# Zypher_PCB.net
KiCad netlist of a schematic drawn in EAGLE
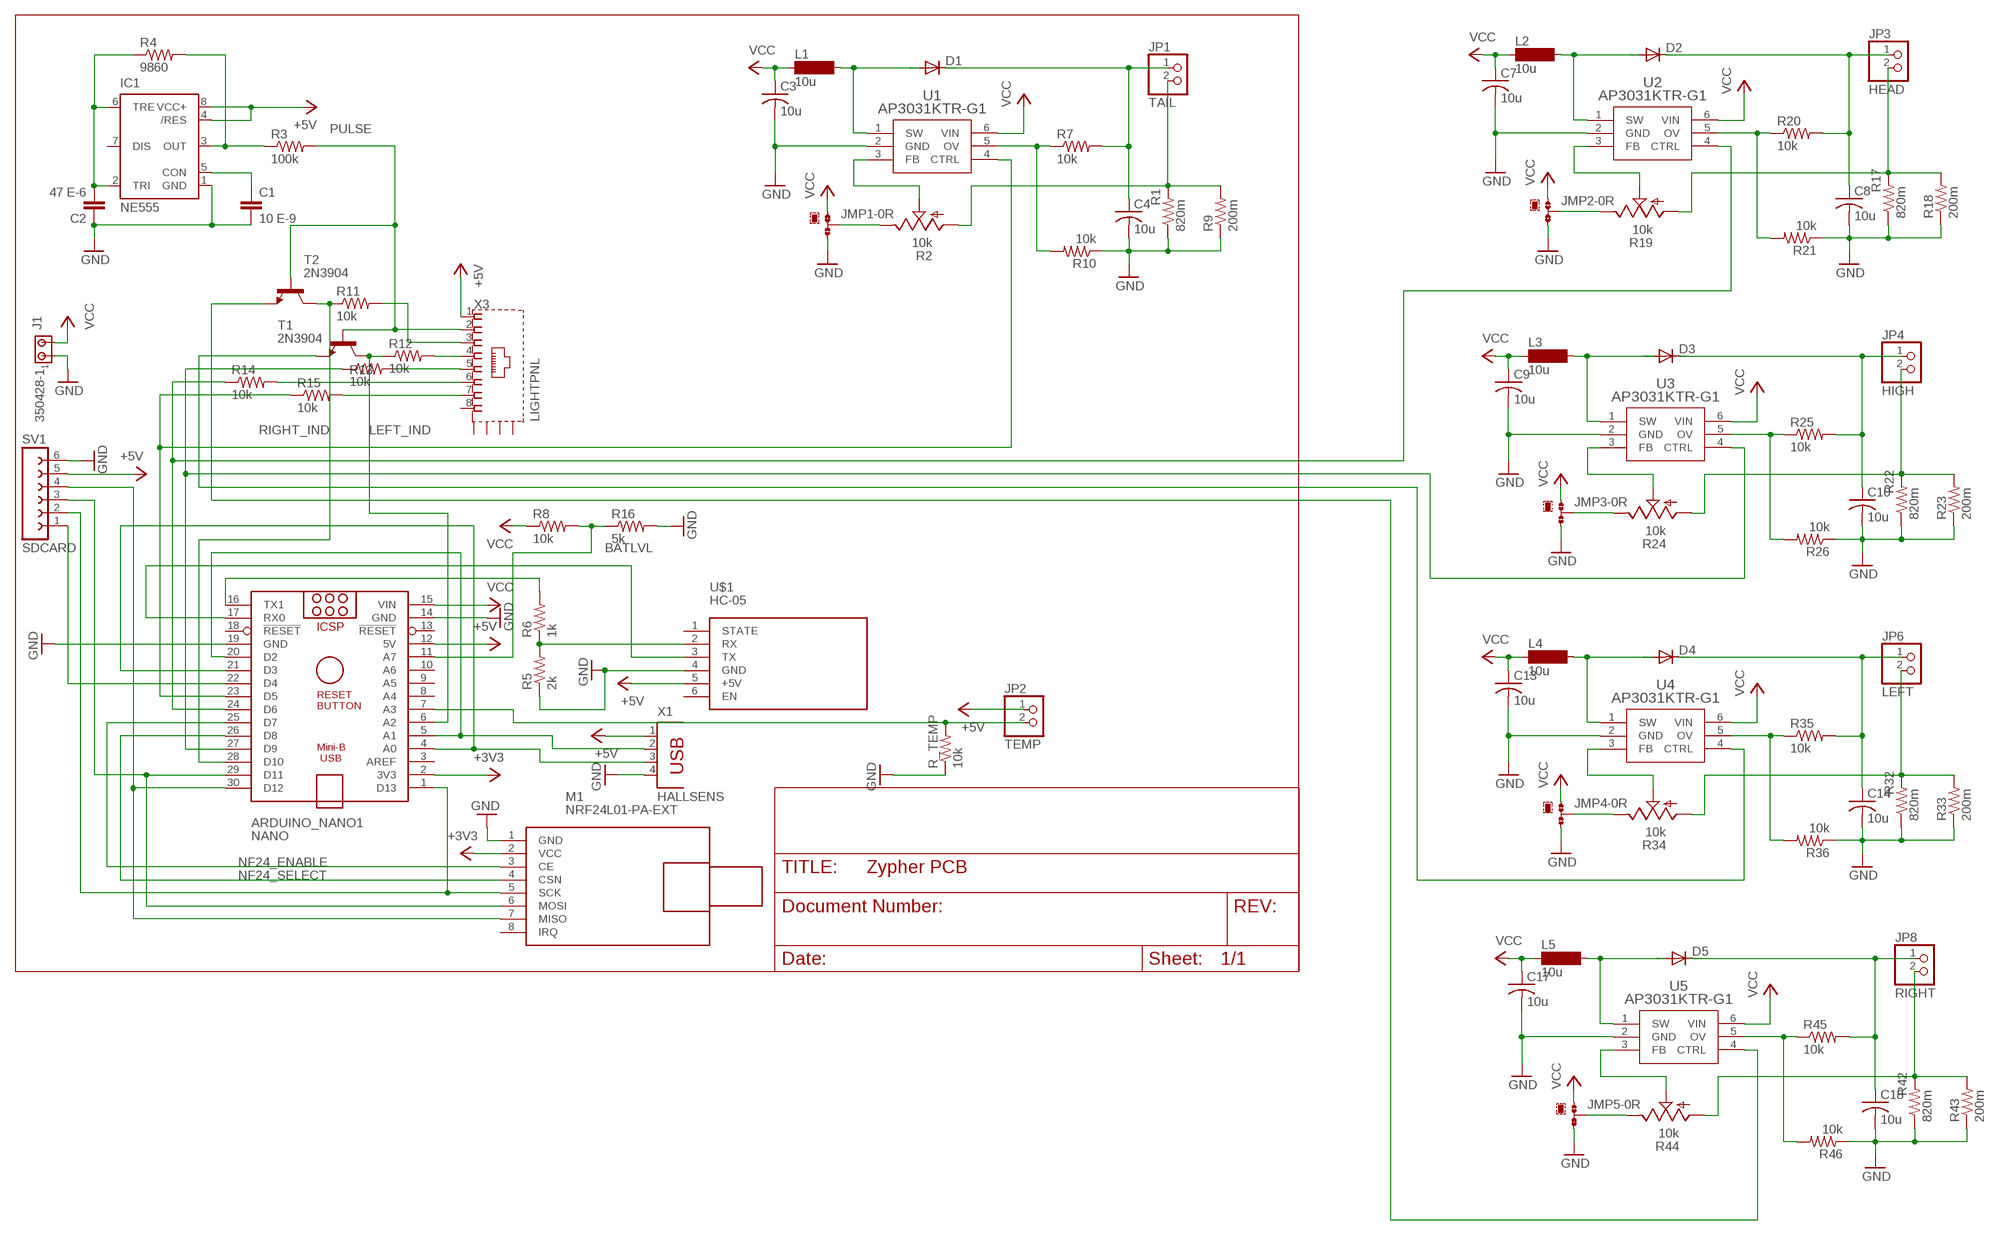
[diagram p0: schematic, sheet 1]

(export (version "E")
  (design (tool "Eeschema 10.0.6"))
  (components
    (comp (ref "ARDUINO_NANO1")
      (value "NANO")
      (footprint "eagle-import:ARDUINO_NANO")
      (libsource (lib "eagle-import") (part "ARDUINO_NANO"))
    )
    (comp (ref "C1")
      (value "10 E-9")
      (footprint "eagle-import:C2.5-5")
      (libsource (lib "eagle-import") (part "C2.5/5"))
    )
    (comp (ref "C2")
      (value "47 E-6")
      (footprint "eagle-import:C2.5-5")
      (libsource (lib "eagle-import") (part "C2.5/5"))
    )
    (comp (ref "C3")
      (value "10u")
      (footprint "eagle-import:C1206K")
      (libsource (lib "eagle-import") (part "C-USC1206K"))
    )
    (comp (ref "C4")
      (value "10u")
      (footprint "eagle-import:C1206K")
      (libsource (lib "eagle-import") (part "C-USC1206K"))
    )
    (comp (ref "C7")
      (value "10u")
      (footprint "eagle-import:C1206K")
      (libsource (lib "eagle-import") (part "C-USC1206K"))
    )
    (comp (ref "C8")
      (value "10u")
      (footprint "eagle-import:C1206K")
      (libsource (lib "eagle-import") (part "C-USC1206K"))
    )
    (comp (ref "C9")
      (value "10u")
      (footprint "eagle-import:C1206K")
      (libsource (lib "eagle-import") (part "C-USC1206K"))
    )
    (comp (ref "C10")
      (value "10u")
      (footprint "eagle-import:C1206K")
      (libsource (lib "eagle-import") (part "C-USC1206K"))
    )
    (comp (ref "C13")
      (value "10u")
      (footprint "eagle-import:C1206K")
      (libsource (lib "eagle-import") (part "C-USC1206K"))
    )
    (comp (ref "C14")
      (value "10u")
      (footprint "eagle-import:C1206K")
      (libsource (lib "eagle-import") (part "C-USC1206K"))
    )
    (comp (ref "C17")
      (value "10u")
      (footprint "eagle-import:C1206K")
      (libsource (lib "eagle-import") (part "C-USC1206K"))
    )
    (comp (ref "C18")
      (value "10u")
      (footprint "eagle-import:C1206K")
      (libsource (lib "eagle-import") (part "C-USC1206K"))
    )
    (comp (ref "D1")
      (value "DIODE-DO-214AC")
      (footprint "eagle-import:DO-214AC")
      (libsource (lib "eagle-import") (part "DIODE-DO-214AC"))
    )
    (comp (ref "D2")
      (value "DIODE-DO-214AC")
      (footprint "eagle-import:DO-214AC")
      (libsource (lib "eagle-import") (part "DIODE-DO-214AC"))
    )
    (comp (ref "D3")
      (value "DIODE-DO-214AC")
      (footprint "eagle-import:DO-214AC")
      (libsource (lib "eagle-import") (part "DIODE-DO-214AC"))
    )
    (comp (ref "D4")
      (value "DIODE-DO-214AC")
      (footprint "eagle-import:DO-214AC")
      (libsource (lib "eagle-import") (part "DIODE-DO-214AC"))
    )
    (comp (ref "D5")
      (value "DIODE-DO-214AC")
      (footprint "eagle-import:DO-214AC")
      (libsource (lib "eagle-import") (part "DIODE-DO-214AC"))
    )
    (comp (ref "IC1")
      (value "NE555")
      (footprint "eagle-import:DIL-08")
      (fields (field (name "MF") "Arrow Electronics") (field (name "MPN") "NE555N"))
      (libsource (lib "eagle-import") (part "NE555"))
    )
    (comp (ref "J1")
      (value "350428-1")
      (footprint "eagle-import:350428-1")
      (libsource (lib "eagle-import") (part "350428-1"))
    )
    (comp (ref "JMP1")
      (value "0R-JUMPA")
      (footprint "eagle-import:A0R-JMP")
      (libsource (lib "eagle-import") (part "0R-JUMPA"))
    )
    (comp (ref "JMP2")
      (value "0R-JUMPA")
      (footprint "eagle-import:A0R-JMP")
      (libsource (lib "eagle-import") (part "0R-JUMPA"))
    )
    (comp (ref "JMP3")
      (value "0R-JUMPA")
      (footprint "eagle-import:A0R-JMP")
      (libsource (lib "eagle-import") (part "0R-JUMPA"))
    )
    (comp (ref "JMP4")
      (value "0R-JUMPA")
      (footprint "eagle-import:A0R-JMP")
      (libsource (lib "eagle-import") (part "0R-JUMPA"))
    )
    (comp (ref "JMP5")
      (value "0R-JUMPA")
      (footprint "eagle-import:A0R-JMP")
      (libsource (lib "eagle-import") (part "0R-JUMPA"))
    )
    (comp (ref "JP1")
      (value "TAIL")
      (footprint "eagle-import:1X02")
      (libsource (lib "eagle-import") (part "PINHD-1X2"))
    )
    (comp (ref "JP2")
      (value "TEMP")
      (footprint "eagle-import:1X02")
      (libsource (lib "eagle-import") (part "PINHD-1X2"))
    )
    (comp (ref "JP3")
      (value "HEAD")
      (footprint "eagle-import:1X02")
      (libsource (lib "eagle-import") (part "PINHD-1X2"))
    )
    (comp (ref "JP4")
      (value "HIGH")
      (footprint "eagle-import:1X02")
      (libsource (lib "eagle-import") (part "PINHD-1X2"))
    )
    (comp (ref "JP6")
      (value "LEFT")
      (footprint "eagle-import:1X02")
      (libsource (lib "eagle-import") (part "PINHD-1X2"))
    )
    (comp (ref "JP8")
      (value "RIGHT")
      (footprint "eagle-import:1X02")
      (libsource (lib "eagle-import") (part "PINHD-1X2"))
    )
    (comp (ref "L1")
      (value "10u")
      (footprint "eagle-import:SD12K100")
      (libsource (lib "eagle-import") (part "SD12K100"))
    )
    (comp (ref "L2")
      (value "10u")
      (footprint "eagle-import:SD12K100")
      (libsource (lib "eagle-import") (part "SD12K100"))
    )
    (comp (ref "L3")
      (value "10u")
      (footprint "eagle-import:SD12K100")
      (libsource (lib "eagle-import") (part "SD12K100"))
    )
    (comp (ref "L4")
      (value "10u")
      (footprint "eagle-import:SD12K100")
      (libsource (lib "eagle-import") (part "SD12K100"))
    )
    (comp (ref "L5")
      (value "10u")
      (footprint "eagle-import:SD12K100")
      (libsource (lib "eagle-import") (part "SD12K100"))
    )
    (comp (ref "M1")
      (value "NRF24L01-PA-EXT")
      (footprint "eagle-import:WIRELESS-NRF24L01-PA-EXT")
      (libsource (lib "eagle-import") (part "WIRELESS-NRF24L01-PA-EXT"))
    )
    (comp (ref "R1")
      (value "820m")
      (footprint "eagle-import:R0603")
      (libsource (lib "eagle-import") (part "resistor_348_R-US_R0603"))
    )
    (comp (ref "R2")
      (value "10k")
      (footprint "eagle-import:RJ9W")
      (libsource (lib "eagle-import") (part "TRIM_US-RJ9W"))
    )
    (comp (ref "R3")
      (value "100k")
      (footprint "eagle-import:0207_7")
      (libsource (lib "eagle-import") (part "R-US_0207/7"))
    )
    (comp (ref "R4")
      (value "9860")
      (footprint "eagle-import:0207_7")
      (libsource (lib "eagle-import") (part "R-US_0207/7"))
    )
    (comp (ref "R5")
      (value "2k")
      (footprint "eagle-import:0204_7")
      (libsource (lib "eagle-import") (part "R-US_0204/7"))
    )
    (comp (ref "R6")
      (value "1k")
      (footprint "eagle-import:0204_7")
      (libsource (lib "eagle-import") (part "R-US_0204/7"))
    )
    (comp (ref "R7")
      (value "10k")
      (footprint "eagle-import:0207_2V")
      (libsource (lib "eagle-import") (part "resistor_348_R-US_0207/2V"))
    )
    (comp (ref "R8")
      (value "10k")
      (footprint "eagle-import:0207_7")
      (libsource (lib "eagle-import") (part "R-US_0207/7"))
    )
    (comp (ref "R9")
      (value "200m")
      (footprint "eagle-import:R0805")
      (libsource (lib "eagle-import") (part "resistor_348_R-US_R0805"))
    )
    (comp (ref "R10")
      (value "10k")
      (footprint "eagle-import:0207_2V")
      (libsource (lib "eagle-import") (part "resistor_348_R-US_0207/2V"))
    )
    (comp (ref "R11")
      (value "10k")
      (footprint "eagle-import:0207_7")
      (libsource (lib "eagle-import") (part "R-US_0207/7"))
    )
    (comp (ref "R12")
      (value "10k")
      (footprint "eagle-import:0207_7")
      (libsource (lib "eagle-import") (part "R-US_0207/7"))
    )
    (comp (ref "R13")
      (value "10k")
      (footprint "eagle-import:0207_7")
      (libsource (lib "eagle-import") (part "R-US_0207/7"))
    )
    (comp (ref "R14")
      (value "10k")
      (footprint "eagle-import:0207_7")
      (libsource (lib "eagle-import") (part "R-US_0207/7"))
    )
    (comp (ref "R15")
      (value "10k")
      (footprint "eagle-import:0207_7")
      (libsource (lib "eagle-import") (part "R-US_0207/7"))
    )
    (comp (ref "R16")
      (value "5k")
      (footprint "eagle-import:0207_7")
      (libsource (lib "eagle-import") (part "R-US_0207/7"))
    )
    (comp (ref "R17")
      (value "820m")
      (footprint "eagle-import:R0603")
      (libsource (lib "eagle-import") (part "resistor_348_R-US_R0603"))
    )
    (comp (ref "R18")
      (value "200m")
      (footprint "eagle-import:R0805")
      (libsource (lib "eagle-import") (part "resistor_348_R-US_R0805"))
    )
    (comp (ref "R19")
      (value "10k")
      (footprint "eagle-import:RJ9W")
      (libsource (lib "eagle-import") (part "TRIM_US-RJ9W"))
    )
    (comp (ref "R20")
      (value "10k")
      (footprint "eagle-import:0207_2V")
      (libsource (lib "eagle-import") (part "resistor_348_R-US_0207/2V"))
    )
    (comp (ref "R21")
      (value "10k")
      (footprint "eagle-import:0207_2V")
      (libsource (lib "eagle-import") (part "resistor_348_R-US_0207/2V"))
    )
    (comp (ref "R22")
      (value "820m")
      (footprint "eagle-import:R0603")
      (libsource (lib "eagle-import") (part "resistor_348_R-US_R0603"))
    )
    (comp (ref "R23")
      (value "200m")
      (footprint "eagle-import:R0805")
      (libsource (lib "eagle-import") (part "resistor_348_R-US_R0805"))
    )
    (comp (ref "R24")
      (value "10k")
      (footprint "eagle-import:RJ9W")
      (libsource (lib "eagle-import") (part "TRIM_US-RJ9W"))
    )
    (comp (ref "R25")
      (value "10k")
      (footprint "eagle-import:0207_2V")
      (libsource (lib "eagle-import") (part "resistor_348_R-US_0207/2V"))
    )
    (comp (ref "R26")
      (value "10k")
      (footprint "eagle-import:0207_2V")
      (libsource (lib "eagle-import") (part "resistor_348_R-US_0207/2V"))
    )
    (comp (ref "R32")
      (value "820m")
      (footprint "eagle-import:R0603")
      (libsource (lib "eagle-import") (part "resistor_348_R-US_R0603"))
    )
    (comp (ref "R33")
      (value "200m")
      (footprint "eagle-import:R0805")
      (libsource (lib "eagle-import") (part "resistor_348_R-US_R0805"))
    )
    (comp (ref "R34")
      (value "10k")
      (footprint "eagle-import:RJ9W")
      (libsource (lib "eagle-import") (part "TRIM_US-RJ9W"))
    )
    (comp (ref "R35")
      (value "10k")
      (footprint "eagle-import:0207_2V")
      (libsource (lib "eagle-import") (part "resistor_348_R-US_0207/2V"))
    )
    (comp (ref "R36")
      (value "10k")
      (footprint "eagle-import:0207_2V")
      (libsource (lib "eagle-import") (part "resistor_348_R-US_0207/2V"))
    )
    (comp (ref "R42")
      (value "820m")
      (footprint "eagle-import:R0603")
      (libsource (lib "eagle-import") (part "resistor_348_R-US_R0603"))
    )
    (comp (ref "R43")
      (value "200m")
      (footprint "eagle-import:R0805")
      (libsource (lib "eagle-import") (part "resistor_348_R-US_R0805"))
    )
    (comp (ref "R44")
      (value "10k")
      (footprint "eagle-import:RJ9W")
      (libsource (lib "eagle-import") (part "TRIM_US-RJ9W"))
    )
    (comp (ref "R45")
      (value "10k")
      (footprint "eagle-import:0207_2V")
      (libsource (lib "eagle-import") (part "resistor_348_R-US_0207/2V"))
    )
    (comp (ref "R46")
      (value "10k")
      (footprint "eagle-import:0207_2V")
      (libsource (lib "eagle-import") (part "resistor_348_R-US_0207/2V"))
    )
    (comp (ref "R_TEMP")
      (value "10k")
      (footprint "eagle-import:0207_7")
      (libsource (lib "eagle-import") (part "R-US_0207/7"))
    )
    (comp (ref "SV1")
      (value "SDCARD")
      (footprint "eagle-import:FE06W")
      (libsource (lib "eagle-import") (part "FE06W"))
    )
    (comp (ref "T1")
      (value "2N3904")
      (footprint "eagle-import:TO92")
      (libsource (lib "eagle-import") (part "2N3904"))
    )
    (comp (ref "T2")
      (value "2N3904")
      (footprint "eagle-import:TO92")
      (libsource (lib "eagle-import") (part "2N3904"))
    )
    (comp (ref "U$1")
      (value "HC-05")
      (footprint "eagle-import:WIRELESS-BLUETOOTH-HC-05")
      (libsource (lib "eagle-import") (part "WIRELESS-BLUETOOTH-HC-05"))
    )
    (comp (ref "U1")
      (value "AP3031KTR-G1")
      (footprint "eagle-import:SOT23-6")
      (fields (field (name "MANUFACTURER_PART_NUMBER") "AP3031KTRG1"))
      (libsource (lib "eagle-import") (part "AP3031KTR-G1"))
    )
    (comp (ref "U2")
      (value "AP3031KTR-G1")
      (footprint "eagle-import:SOT23-6")
      (fields (field (name "MANUFACTURER_PART_NUMBER") "AP3031KTRG1"))
      (libsource (lib "eagle-import") (part "AP3031KTR-G1"))
    )
    (comp (ref "U3")
      (value "AP3031KTR-G1")
      (footprint "eagle-import:SOT23-6")
      (fields (field (name "MANUFACTURER_PART_NUMBER") "AP3031KTRG1"))
      (libsource (lib "eagle-import") (part "AP3031KTR-G1"))
    )
    (comp (ref "U4")
      (value "AP3031KTR-G1")
      (footprint "eagle-import:SOT23-6")
      (fields (field (name "MANUFACTURER_PART_NUMBER") "AP3031KTRG1"))
      (libsource (lib "eagle-import") (part "AP3031KTR-G1"))
    )
    (comp (ref "U5")
      (value "AP3031KTR-G1")
      (footprint "eagle-import:SOT23-6")
      (fields (field (name "MANUFACTURER_PART_NUMBER") "AP3031KTRG1"))
      (libsource (lib "eagle-import") (part "AP3031KTR-G1"))
    )
    (comp (ref "X1")
      (value "HALLSENS")
      (footprint "eagle-import:PN87520")
      (libsource (lib "eagle-import") (part "PN87520"))
    )
    (comp (ref "X3")
      (value "LIGHTPNL")
      (footprint "eagle-import:RJ45-SHIELD1")
      (libsource (lib "eagle-import") (part "RJ4521-S-6L"))
    )
  )
  (nets
    (net (code "1") (name "+3V3") (class "Default")
      (node (ref "ARDUINO_NANO1") (pin "2") (pinfunction "3V3_2") (pintype "output"))
      (node (ref "M1") (pin "2") (pinfunction "VCC_2") (pintype "power_in"))
    )
    (net (code "2") (name "+5V") (class "Default")
      (node (ref "ARDUINO_NANO1") (pin "12") (pinfunction "5V_12") (pintype "power_in"))
      (node (ref "IC1") (pin "4") (pinfunction "/RES_4") (pintype "input"))
      (node (ref "IC1") (pin "8") (pinfunction "VCC+_8") (pintype "power_in"))
      (node (ref "JP2") (pin "1") (pinfunction "1_1") (pintype "passive"))
      (node (ref "SV1") (pin "5") (pinfunction "5_5") (pintype "passive"))
      (node (ref "U$1") (pin "5") (pinfunction "+5V_5") (pintype "power_in"))
      (node (ref "X1") (pin "1") (pinfunction "1_1") (pintype "passive"))
      (node (ref "X3") (pin "1") (pinfunction "1_1") (pintype "passive"))
    )
    (net (code "3") (name "/BATLVL") (class "Default")
      (node (ref "ARDUINO_NANO1") (pin "11") (pinfunction "A7_11") (pintype "bidirectional"))
      (node (ref "R16") (pin "1") (pinfunction "1_1") (pintype "passive"))
      (node (ref "R8") (pin "2") (pinfunction "2_2") (pintype "passive"))
    )
    (net (code "4") (name "/LEFT_IND") (class "Default")
      (node (ref "ARDUINO_NANO1") (pin "6") (pinfunction "A2_6") (pintype "bidirectional"))
      (node (ref "R12") (pin "1") (pinfunction "1_1") (pintype "passive"))
      (node (ref "T1") (pin "1") (pinfunction "C_1") (pintype "passive"))
    )
    (net (code "5") (name "/NF24_ENABLE") (class "Default")
      (node (ref "ARDUINO_NANO1") (pin "25") (pinfunction "D7_25") (pintype "bidirectional"))
      (node (ref "M1") (pin "3") (pinfunction "CE_3") (pintype "bidirectional"))
    )
    (net (code "6") (name "/NF24_SELECT") (class "Default")
      (node (ref "ARDUINO_NANO1") (pin "26") (pinfunction "D8_26") (pintype "bidirectional"))
      (node (ref "M1") (pin "4") (pinfunction "CSN_4") (pintype "bidirectional"))
    )
    (net (code "7") (name "/PULSE") (class "Default")
      (node (ref "R3") (pin "2") (pinfunction "2_2") (pintype "passive"))
      (node (ref "T1") (pin "2") (pinfunction "B_2") (pintype "passive"))
      (node (ref "T2") (pin "2") (pinfunction "B_2") (pintype "passive"))
      (node (ref "X3") (pin "2") (pinfunction "2_2") (pintype "passive"))
    )
    (net (code "8") (name "/RIGHT_IND") (class "Default")
      (node (ref "ARDUINO_NANO1") (pin "28") (pinfunction "D10_28") (pintype "bidirectional"))
      (node (ref "R11") (pin "1") (pinfunction "1_1") (pintype "passive"))
      (node (ref "T2") (pin "1") (pinfunction "C_1") (pintype "passive"))
    )
    (net (code "9") (name "GND") (class "Default")
      (node (ref "ARDUINO_NANO1") (pin "14") (pinfunction "GND_14") (pintype "power_in"))
      (node (ref "ARDUINO_NANO1") (pin "19") (pinfunction "GND_19") (pintype "power_in"))
      (node (ref "C1") (pin "2") (pinfunction "2_2") (pintype "passive"))
      (node (ref "C10") (pin "2") (pinfunction "2_2") (pintype "passive"))
      (node (ref "C13") (pin "2") (pinfunction "2_2") (pintype "passive"))
      (node (ref "C14") (pin "2") (pinfunction "2_2") (pintype "passive"))
      (node (ref "C17") (pin "2") (pinfunction "2_2") (pintype "passive"))
      (node (ref "C18") (pin "2") (pinfunction "2_2") (pintype "passive"))
      (node (ref "C2") (pin "1") (pinfunction "1_1") (pintype "passive"))
      (node (ref "C3") (pin "2") (pinfunction "2_2") (pintype "passive"))
      (node (ref "C4") (pin "2") (pinfunction "2_2") (pintype "passive"))
      (node (ref "C7") (pin "2") (pinfunction "2_2") (pintype "passive"))
      (node (ref "C8") (pin "2") (pinfunction "2_2") (pintype "passive"))
      (node (ref "C9") (pin "2") (pinfunction "2_2") (pintype "passive"))
      (node (ref "IC1") (pin "1") (pinfunction "GND_1") (pintype "power_in"))
      (node (ref "J1") (pin "1") (pinfunction "1_1") (pintype "passive"))
      (node (ref "JMP1") (pin "3") (pinfunction "3_3") (pintype "passive"))
      (node (ref "JMP2") (pin "3") (pinfunction "3_3") (pintype "passive"))
      (node (ref "JMP3") (pin "3") (pinfunction "3_3") (pintype "passive"))
      (node (ref "JMP4") (pin "3") (pinfunction "3_3") (pintype "passive"))
      (node (ref "JMP5") (pin "3") (pinfunction "3_3") (pintype "passive"))
      (node (ref "M1") (pin "1") (pinfunction "GND_1") (pintype "power_in"))
      (node (ref "R1") (pin "1") (pinfunction "1_1") (pintype "passive"))
      (node (ref "R10") (pin "1") (pinfunction "1_1") (pintype "passive"))
      (node (ref "R16") (pin "2") (pinfunction "2_2") (pintype "passive"))
      (node (ref "R17") (pin "1") (pinfunction "1_1") (pintype "passive"))
      (node (ref "R18") (pin "1") (pinfunction "1_1") (pintype "passive"))
      (node (ref "R21") (pin "1") (pinfunction "1_1") (pintype "passive"))
      (node (ref "R22") (pin "1") (pinfunction "1_1") (pintype "passive"))
      (node (ref "R23") (pin "1") (pinfunction "1_1") (pintype "passive"))
      (node (ref "R26") (pin "1") (pinfunction "1_1") (pintype "passive"))
      (node (ref "R32") (pin "1") (pinfunction "1_1") (pintype "passive"))
      (node (ref "R33") (pin "1") (pinfunction "1_1") (pintype "passive"))
      (node (ref "R36") (pin "1") (pinfunction "1_1") (pintype "passive"))
      (node (ref "R42") (pin "1") (pinfunction "1_1") (pintype "passive"))
      (node (ref "R43") (pin "1") (pinfunction "1_1") (pintype "passive"))
      (node (ref "R46") (pin "1") (pinfunction "1_1") (pintype "passive"))
      (node (ref "R5") (pin "1") (pinfunction "1_1") (pintype "passive"))
      (node (ref "R9") (pin "1") (pinfunction "1_1") (pintype "passive"))
      (node (ref "R_TEMP") (pin "1") (pinfunction "1_1") (pintype "passive"))
      (node (ref "SV1") (pin "6") (pinfunction "6_6") (pintype "passive"))
      (node (ref "U$1") (pin "4") (pinfunction "GND_4") (pintype "power_in"))
      (node (ref "U1") (pin "2") (pinfunction "GND_2") (pintype "power_in"))
      (node (ref "U2") (pin "2") (pinfunction "GND_2") (pintype "power_in"))
      (node (ref "U3") (pin "2") (pinfunction "GND_2") (pintype "power_in"))
      (node (ref "U4") (pin "2") (pinfunction "GND_2") (pintype "power_in"))
      (node (ref "U5") (pin "2") (pinfunction "GND_2") (pintype "power_in"))
      (node (ref "X1") (pin "4") (pinfunction "4_4") (pintype "passive"))
    )
    (net (code "10") (name "Net-(ARDUINO_NANO1-A0)") (class "Default")
      (node (ref "ARDUINO_NANO1") (pin "21") (pinfunction "D3_21") (pintype "bidirectional"))
      (node (ref "ARDUINO_NANO1") (pin "4") (pinfunction "A0_4") (pintype "bidirectional"))
      (node (ref "X1") (pin "3") (pinfunction "3_3") (pintype "passive"))
    )
    (net (code "11") (name "Net-(ARDUINO_NANO1-A1)") (class "Default")
      (node (ref "ARDUINO_NANO1") (pin "20") (pinfunction "D2_20") (pintype "bidirectional"))
      (node (ref "ARDUINO_NANO1") (pin "5") (pinfunction "A1_5") (pintype "bidirectional"))
      (node (ref "X1") (pin "2") (pinfunction "2_2") (pintype "passive"))
    )
    (net (code "12") (name "Net-(ARDUINO_NANO1-A3)") (class "Default")
      (node (ref "ARDUINO_NANO1") (pin "7") (pinfunction "A3_7") (pintype "bidirectional"))
      (node (ref "JP2") (pin "2") (pinfunction "2_2") (pintype "passive"))
      (node (ref "R_TEMP") (pin "2") (pinfunction "2_2") (pintype "passive"))
    )
    (net (code "13") (name "Net-(ARDUINO_NANO1-D4)") (class "Default")
      (node (ref "ARDUINO_NANO1") (pin "22") (pinfunction "D4_22") (pintype "bidirectional"))
      (node (ref "SV1") (pin "1") (pinfunction "1_1") (pintype "passive"))
    )
    (net (code "14") (name "Net-(ARDUINO_NANO1-D5)") (class "Default")
      (node (ref "ARDUINO_NANO1") (pin "23") (pinfunction "D5_23") (pintype "bidirectional"))
      (node (ref "R15") (pin "1") (pinfunction "1_1") (pintype "passive"))
      (node (ref "U1") (pin "4") (pinfunction "CTRL_4") (pintype "passive"))
    )
    (net (code "15") (name "Net-(ARDUINO_NANO1-D6)") (class "Default")
      (node (ref "ARDUINO_NANO1") (pin "24") (pinfunction "D6_24") (pintype "bidirectional"))
      (node (ref "R14") (pin "1") (pinfunction "1_1") (pintype "passive"))
      (node (ref "U2") (pin "4") (pinfunction "CTRL_4") (pintype "passive"))
    )
    (net (code "16") (name "Net-(ARDUINO_NANO1-D9)") (class "Default")
      (node (ref "ARDUINO_NANO1") (pin "27") (pinfunction "D9_27") (pintype "bidirectional"))
      (node (ref "R13") (pin "1") (pinfunction "1_1") (pintype "passive"))
      (node (ref "U3") (pin "4") (pinfunction "CTRL_4") (pintype "passive"))
    )
    (net (code "17") (name "Net-(ARDUINO_NANO1-D11)") (class "Default")
      (node (ref "ARDUINO_NANO1") (pin "29") (pinfunction "D11_29") (pintype "bidirectional"))
      (node (ref "M1") (pin "6") (pinfunction "MOSI_6") (pintype "bidirectional"))
      (node (ref "SV1") (pin "3") (pinfunction "3_3") (pintype "passive"))
    )
    (net (code "18") (name "Net-(ARDUINO_NANO1-D12)") (class "Default")
      (node (ref "ARDUINO_NANO1") (pin "30") (pinfunction "D12_30") (pintype "bidirectional"))
      (node (ref "M1") (pin "7") (pinfunction "MISO_7") (pintype "bidirectional"))
      (node (ref "SV1") (pin "4") (pinfunction "4_4") (pintype "passive"))
    )
    (net (code "19") (name "Net-(ARDUINO_NANO1-D13)") (class "Default")
      (node (ref "ARDUINO_NANO1") (pin "1") (pinfunction "D13_1") (pintype "bidirectional"))
      (node (ref "M1") (pin "5") (pinfunction "SCK_5") (pintype "bidirectional"))
      (node (ref "SV1") (pin "2") (pinfunction "2_2") (pintype "passive"))
    )
    (net (code "20") (name "Net-(ARDUINO_NANO1-RX0)") (class "Default")
      (node (ref "ARDUINO_NANO1") (pin "17") (pinfunction "RX0_17") (pintype "bidirectional"))
      (node (ref "U$1") (pin "3") (pinfunction "TX_3") (pintype "bidirectional"))
    )
    (net (code "21") (name "Net-(ARDUINO_NANO1-TX1)") (class "Default")
      (node (ref "ARDUINO_NANO1") (pin "16") (pinfunction "TX1_16") (pintype "bidirectional"))
      (node (ref "R6") (pin "2") (pinfunction "2_2") (pintype "passive"))
    )
    (net (code "22") (name "Net-(C4-Pad1)") (class "Default")
      (node (ref "C4") (pin "1") (pinfunction "1_1") (pintype "passive"))
      (node (ref "D1") (pin "C") (pinfunction "C_C") (pintype "passive"))
      (node (ref "JP1") (pin "1") (pinfunction "1_1") (pintype "passive"))
      (node (ref "R7") (pin "2") (pinfunction "2_2") (pintype "passive"))
    )
    (net (code "23") (name "Net-(C8-Pad1)") (class "Default")
      (node (ref "C8") (pin "1") (pinfunction "1_1") (pintype "passive"))
      (node (ref "D2") (pin "C") (pinfunction "C_C") (pintype "passive"))
      (node (ref "JP3") (pin "1") (pinfunction "1_1") (pintype "passive"))
      (node (ref "R20") (pin "2") (pinfunction "2_2") (pintype "passive"))
    )
    (net (code "24") (name "Net-(C10-Pad1)") (class "Default")
      (node (ref "C10") (pin "1") (pinfunction "1_1") (pintype "passive"))
      (node (ref "D3") (pin "C") (pinfunction "C_C") (pintype "passive"))
      (node (ref "JP4") (pin "1") (pinfunction "1_1") (pintype "passive"))
      (node (ref "R25") (pin "2") (pinfunction "2_2") (pintype "passive"))
    )
    (net (code "25") (name "Net-(C14-Pad1)") (class "Default")
      (node (ref "C14") (pin "1") (pinfunction "1_1") (pintype "passive"))
      (node (ref "D4") (pin "C") (pinfunction "C_C") (pintype "passive"))
      (node (ref "JP6") (pin "1") (pinfunction "1_1") (pintype "passive"))
      (node (ref "R35") (pin "2") (pinfunction "2_2") (pintype "passive"))
    )
    (net (code "26") (name "Net-(C18-Pad1)") (class "Default")
      (node (ref "C18") (pin "1") (pinfunction "1_1") (pintype "passive"))
      (node (ref "D5") (pin "C") (pinfunction "C_C") (pintype "passive"))
      (node (ref "JP8") (pin "1") (pinfunction "1_1") (pintype "passive"))
      (node (ref "R45") (pin "2") (pinfunction "2_2") (pintype "passive"))
    )
    (net (code "27") (name "Net-(IC1-CON)") (class "Default")
      (node (ref "C1") (pin "1") (pinfunction "1_1") (pintype "passive"))
      (node (ref "IC1") (pin "5") (pinfunction "CON_5") (pintype "input"))
    )
    (net (code "28") (name "Net-(IC1-OUT)") (class "Default")
      (node (ref "IC1") (pin "3") (pinfunction "OUT_3") (pintype "output"))
      (node (ref "R3") (pin "1") (pinfunction "1_1") (pintype "passive"))
      (node (ref "R4") (pin "2") (pinfunction "2_2") (pintype "passive"))
    )
    (net (code "29") (name "Net-(IC1-TRE)") (class "Default")
      (node (ref "C2") (pin "2") (pinfunction "2_2") (pintype "passive"))
      (node (ref "IC1") (pin "2") (pinfunction "TRI_2") (pintype "input"))
      (node (ref "IC1") (pin "6") (pinfunction "TRE_6") (pintype "input"))
      (node (ref "R4") (pin "1") (pinfunction "1_1") (pintype "passive"))
    )
    (net (code "30") (name "Net-(JMP1-Pad2)") (class "Default")
      (node (ref "JMP1") (pin "2") (pinfunction "2_2") (pintype "passive"))
      (node (ref "R2") (pin "E") (pinfunction "E_E") (pintype "passive"))
    )
    (net (code "31") (name "Net-(JMP2-Pad2)") (class "Default")
      (node (ref "JMP2") (pin "2") (pinfunction "2_2") (pintype "passive"))
      (node (ref "R19") (pin "E") (pinfunction "E_E") (pintype "passive"))
    )
    (net (code "32") (name "Net-(JMP3-Pad2)") (class "Default")
      (node (ref "JMP3") (pin "2") (pinfunction "2_2") (pintype "passive"))
      (node (ref "R24") (pin "E") (pinfunction "E_E") (pintype "passive"))
    )
    (net (code "33") (name "Net-(JMP4-Pad2)") (class "Default")
      (node (ref "JMP4") (pin "2") (pinfunction "2_2") (pintype "passive"))
      (node (ref "R34") (pin "E") (pinfunction "E_E") (pintype "passive"))
    )
    (net (code "34") (name "Net-(JMP5-Pad2)") (class "Default")
      (node (ref "JMP5") (pin "2") (pinfunction "2_2") (pintype "passive"))
      (node (ref "R44") (pin "E") (pinfunction "E_E") (pintype "passive"))
    )
    (net (code "35") (name "Net-(JP1-Pad2)") (class "Default")
      (node (ref "JP1") (pin "2") (pinfunction "2_2") (pintype "passive"))
      (node (ref "R1") (pin "2") (pinfunction "2_2") (pintype "passive"))
      (node (ref "R2") (pin "A") (pinfunction "A_A") (pintype "passive"))
      (node (ref "R9") (pin "2") (pinfunction "2_2") (pintype "passive"))
    )
    (net (code "36") (name "Net-(JP3-Pad2)") (class "Default")
      (node (ref "JP3") (pin "2") (pinfunction "2_2") (pintype "passive"))
      (node (ref "R17") (pin "2") (pinfunction "2_2") (pintype "passive"))
      (node (ref "R18") (pin "2") (pinfunction "2_2") (pintype "passive"))
      (node (ref "R19") (pin "A") (pinfunction "A_A") (pintype "passive"))
    )
    (net (code "37") (name "Net-(JP4-Pad2)") (class "Default")
      (node (ref "JP4") (pin "2") (pinfunction "2_2") (pintype "passive"))
      (node (ref "R22") (pin "2") (pinfunction "2_2") (pintype "passive"))
      (node (ref "R23") (pin "2") (pinfunction "2_2") (pintype "passive"))
      (node (ref "R24") (pin "A") (pinfunction "A_A") (pintype "passive"))
    )
    (net (code "38") (name "Net-(JP6-Pad2)") (class "Default")
      (node (ref "JP6") (pin "2") (pinfunction "2_2") (pintype "passive"))
      (node (ref "R32") (pin "2") (pinfunction "2_2") (pintype "passive"))
      (node (ref "R33") (pin "2") (pinfunction "2_2") (pintype "passive"))
      (node (ref "R34") (pin "A") (pinfunction "A_A") (pintype "passive"))
    )
    (net (code "39") (name "Net-(JP8-Pad2)") (class "Default")
      (node (ref "JP8") (pin "2") (pinfunction "2_2") (pintype "passive"))
      (node (ref "R42") (pin "2") (pinfunction "2_2") (pintype "passive"))
      (node (ref "R43") (pin "2") (pinfunction "2_2") (pintype "passive"))
      (node (ref "R44") (pin "A") (pinfunction "A_A") (pintype "passive"))
    )
    (net (code "40") (name "Net-(R11-Pad2)") (class "Default")
      (node (ref "R11") (pin "2") (pinfunction "2_2") (pintype "passive"))
      (node (ref "X3") (pin "3") (pinfunction "3_3") (pintype "passive"))
    )
    (net (code "41") (name "Net-(R12-Pad2)") (class "Default")
      (node (ref "R12") (pin "2") (pinfunction "2_2") (pintype "passive"))
      (node (ref "X3") (pin "4") (pinfunction "4_4") (pintype "passive"))
    )
    (net (code "42") (name "Net-(R13-Pad2)") (class "Default")
      (node (ref "R13") (pin "2") (pinfunction "2_2") (pintype "passive"))
      (node (ref "X3") (pin "5") (pinfunction "5_5") (pintype "passive"))
    )
    (net (code "43") (name "Net-(R14-Pad2)") (class "Default")
      (node (ref "R14") (pin "2") (pinfunction "2_2") (pintype "passive"))
      (node (ref "X3") (pin "6") (pinfunction "6_6") (pintype "passive"))
    )
    (net (code "44") (name "Net-(R15-Pad2)") (class "Default")
      (node (ref "R15") (pin "2") (pinfunction "2_2") (pintype "passive"))
      (node (ref "X3") (pin "7") (pinfunction "7_7") (pintype "passive"))
    )
    (net (code "45") (name "Net-(T1-E)") (class "Default")
      (node (ref "T1") (pin "3") (pinfunction "E_3") (pintype "passive"))
      (node (ref "U4") (pin "4") (pinfunction "CTRL_4") (pintype "passive"))
    )
    (net (code "46") (name "Net-(T2-E)") (class "Default")
      (node (ref "T2") (pin "3") (pinfunction "E_3") (pintype "passive"))
      (node (ref "U5") (pin "4") (pinfunction "CTRL_4") (pintype "passive"))
    )
    (net (code "47") (name "Net-(U$1-RX)") (class "Default")
      (node (ref "R5") (pin "2") (pinfunction "2_2") (pintype "passive"))
      (node (ref "R6") (pin "1") (pinfunction "1_1") (pintype "passive"))
      (node (ref "U$1") (pin "2") (pinfunction "RX_2") (pintype "bidirectional"))
    )
    (net (code "48") (name "Net-(U1-FB)") (class "Default")
      (node (ref "R2") (pin "S") (pinfunction "S_S") (pintype "passive"))
      (node (ref "U1") (pin "3") (pinfunction "FB_3") (pintype "output"))
    )
    (net (code "49") (name "Net-(U1-OV)") (class "Default")
      (node (ref "R10") (pin "2") (pinfunction "2_2") (pintype "passive"))
      (node (ref "R7") (pin "1") (pinfunction "1_1") (pintype "passive"))
      (node (ref "U1") (pin "5") (pinfunction "OV_5") (pintype "passive"))
    )
    (net (code "50") (name "Net-(U1-SW)") (class "Default")
      (node (ref "D1") (pin "A") (pinfunction "A_A") (pintype "passive"))
      (node (ref "L1") (pin "2") (pinfunction "2_2") (pintype "passive"))
      (node (ref "U1") (pin "1") (pinfunction "SW_1") (pintype "output"))
    )
    (net (code "51") (name "Net-(U2-FB)") (class "Default")
      (node (ref "R19") (pin "S") (pinfunction "S_S") (pintype "passive"))
      (node (ref "U2") (pin "3") (pinfunction "FB_3") (pintype "output"))
    )
    (net (code "52") (name "Net-(U2-OV)") (class "Default")
      (node (ref "R20") (pin "1") (pinfunction "1_1") (pintype "passive"))
      (node (ref "R21") (pin "2") (pinfunction "2_2") (pintype "passive"))
      (node (ref "U2") (pin "5") (pinfunction "OV_5") (pintype "passive"))
    )
    (net (code "53") (name "Net-(U2-SW)") (class "Default")
      (node (ref "D2") (pin "A") (pinfunction "A_A") (pintype "passive"))
      (node (ref "L2") (pin "2") (pinfunction "2_2") (pintype "passive"))
      (node (ref "U2") (pin "1") (pinfunction "SW_1") (pintype "output"))
    )
    (net (code "54") (name "Net-(U3-FB)") (class "Default")
      (node (ref "R24") (pin "S") (pinfunction "S_S") (pintype "passive"))
      (node (ref "U3") (pin "3") (pinfunction "FB_3") (pintype "output"))
    )
    (net (code "55") (name "Net-(U3-OV)") (class "Default")
      (node (ref "R25") (pin "1") (pinfunction "1_1") (pintype "passive"))
      (node (ref "R26") (pin "2") (pinfunction "2_2") (pintype "passive"))
      (node (ref "U3") (pin "5") (pinfunction "OV_5") (pintype "passive"))
    )
    (net (code "56") (name "Net-(U3-SW)") (class "Default")
      (node (ref "D3") (pin "A") (pinfunction "A_A") (pintype "passive"))
      (node (ref "L3") (pin "2") (pinfunction "2_2") (pintype "passive"))
      (node (ref "U3") (pin "1") (pinfunction "SW_1") (pintype "output"))
    )
    (net (code "57") (name "Net-(U4-FB)") (class "Default")
      (node (ref "R34") (pin "S") (pinfunction "S_S") (pintype "passive"))
      (node (ref "U4") (pin "3") (pinfunction "FB_3") (pintype "output"))
    )
    (net (code "58") (name "Net-(U4-OV)") (class "Default")
      (node (ref "R35") (pin "1") (pinfunction "1_1") (pintype "passive"))
      (node (ref "R36") (pin "2") (pinfunction "2_2") (pintype "passive"))
      (node (ref "U4") (pin "5") (pinfunction "OV_5") (pintype "passive"))
    )
    (net (code "59") (name "Net-(U4-SW)") (class "Default")
      (node (ref "D4") (pin "A") (pinfunction "A_A") (pintype "passive"))
      (node (ref "L4") (pin "2") (pinfunction "2_2") (pintype "passive"))
      (node (ref "U4") (pin "1") (pinfunction "SW_1") (pintype "output"))
    )
    (net (code "60") (name "Net-(U5-FB)") (class "Default")
      (node (ref "R44") (pin "S") (pinfunction "S_S") (pintype "passive"))
      (node (ref "U5") (pin "3") (pinfunction "FB_3") (pintype "output"))
    )
    (net (code "61") (name "Net-(U5-OV)") (class "Default")
      (node (ref "R45") (pin "1") (pinfunction "1_1") (pintype "passive"))
      (node (ref "R46") (pin "2") (pinfunction "2_2") (pintype "passive"))
      (node (ref "U5") (pin "5") (pinfunction "OV_5") (pintype "passive"))
    )
    (net (code "62") (name "Net-(U5-SW)") (class "Default")
      (node (ref "D5") (pin "A") (pinfunction "A_A") (pintype "passive"))
      (node (ref "L5") (pin "2") (pinfunction "2_2") (pintype "passive"))
      (node (ref "U5") (pin "1") (pinfunction "SW_1") (pintype "output"))
    )
    (net (code "63") (name "VCC") (class "Default")
      (node (ref "ARDUINO_NANO1") (pin "15") (pinfunction "VIN_15") (pintype "power_in"))
      (node (ref "C13") (pin "1") (pinfunction "1_1") (pintype "passive"))
      (node (ref "C17") (pin "1") (pinfunction "1_1") (pintype "passive"))
      (node (ref "C3") (pin "1") (pinfunction "1_1") (pintype "passive"))
      (node (ref "C7") (pin "1") (pinfunction "1_1") (pintype "passive"))
      (node (ref "C9") (pin "1") (pinfunction "1_1") (pintype "passive"))
      (node (ref "J1") (pin "2") (pinfunction "2_2") (pintype "passive"))
      (node (ref "JMP1") (pin "1") (pinfunction "1_1") (pintype "passive"))
      (node (ref "JMP2") (pin "1") (pinfunction "1_1") (pintype "passive"))
      (node (ref "JMP3") (pin "1") (pinfunction "1_1") (pintype "passive"))
      (node (ref "JMP4") (pin "1") (pinfunction "1_1") (pintype "passive"))
      (node (ref "JMP5") (pin "1") (pinfunction "1_1") (pintype "passive"))
      (node (ref "L1") (pin "1") (pinfunction "1_1") (pintype "passive"))
      (node (ref "L2") (pin "1") (pinfunction "1_1") (pintype "passive"))
      (node (ref "L3") (pin "1") (pinfunction "1_1") (pintype "passive"))
      (node (ref "L4") (pin "1") (pinfunction "1_1") (pintype "passive"))
      (node (ref "L5") (pin "1") (pinfunction "1_1") (pintype "passive"))
      (node (ref "R8") (pin "1") (pinfunction "1_1") (pintype "passive"))
      (node (ref "U1") (pin "6") (pinfunction "VIN_6") (pintype "input"))
      (node (ref "U2") (pin "6") (pinfunction "VIN_6") (pintype "input"))
      (node (ref "U3") (pin "6") (pinfunction "VIN_6") (pintype "input"))
      (node (ref "U4") (pin "6") (pinfunction "VIN_6") (pintype "input"))
      (node (ref "U5") (pin "6") (pinfunction "VIN_6") (pintype "input"))
    )
    (net (code "64") (name "unconnected-(ARDUINO_NANO1-A4-Pad8)") (class "Default")
      (node (ref "ARDUINO_NANO1") (pin "8") (pinfunction "A4_8") (pintype "bidirectional"))
    )
    (net (code "65") (name "unconnected-(ARDUINO_NANO1-A5-Pad9)") (class "Default")
      (node (ref "ARDUINO_NANO1") (pin "9") (pinfunction "A5_9") (pintype "bidirectional"))
    )
    (net (code "66") (name "unconnected-(ARDUINO_NANO1-A6-Pad10)") (class "Default")
      (node (ref "ARDUINO_NANO1") (pin "10") (pinfunction "A6_10") (pintype "bidirectional"))
    )
    (net (code "67") (name "unconnected-(ARDUINO_NANO1-AREF-Pad3)") (class "Default")
      (node (ref "ARDUINO_NANO1") (pin "3") (pinfunction "AREF_3") (pintype "input"))
    )
    (net (code "68") (name "unconnected-(ARDUINO_NANO1-~{RESET}-Pad13)") (class "Default")
      (node (ref "ARDUINO_NANO1") (pin "13") (pinfunction "~{RESET}_13") (pintype "input"))
    )
    (net (code "69") (name "unconnected-(ARDUINO_NANO1-~{RESET}-Pad18)") (class "Default")
      (node (ref "ARDUINO_NANO1") (pin "18") (pinfunction "~{RESET}_18") (pintype "input"))
    )
    (net (code "70") (name "unconnected-(IC1-DIS-Pad7)") (class "Default")
      (node (ref "IC1") (pin "7") (pinfunction "DIS_7") (pintype "input"))
    )
    (net (code "71") (name "unconnected-(M1-IRQ-Pad8)") (class "Default")
      (node (ref "M1") (pin "8") (pinfunction "IRQ_8") (pintype "bidirectional"))
    )
    (net (code "72") (name "unconnected-(U$1-EN-Pad6)") (class "Default")
      (node (ref "U$1") (pin "6") (pinfunction "EN_6") (pintype "bidirectional"))
    )
    (net (code "73") (name "unconnected-(U$1-STATE-Pad1)") (class "Default")
      (node (ref "U$1") (pin "1") (pinfunction "STATE_1") (pintype "bidirectional"))
    )
    (net (code "74") (name "unconnected-(X3-Pad8)") (class "Default")
      (node (ref "X3") (pin "8") (pinfunction "8_8") (pintype "passive"))
    )
    (net (code "75") (name "unconnected-(X3-S-PadS1)") (class "Default")
      (node (ref "X3") (pin "S1") (pinfunction "S_S1") (pintype "passive"))
    )
    (net (code "76") (name "unconnected-(X3-S-PadS2)") (class "Default")
      (node (ref "X3") (pin "S2") (pinfunction "S_S2") (pintype "passive"))
    )
    (net (code "77") (name "unconnected-(X3-S-PadS3)") (class "Default")
      (node (ref "X3") (pin "S3") (pinfunction "S_S3") (pintype "passive"))
    )
    (net (code "78") (name "unconnected-(X3-S-PadS4)") (class "Default")
      (node (ref "X3") (pin "S4") (pinfunction "S_S4") (pintype "passive"))
    )
  )
)
